# HIM-Otte-server-slow-control-V1-3a.net
KiCad netlist of a schematic drawn in EAGLE
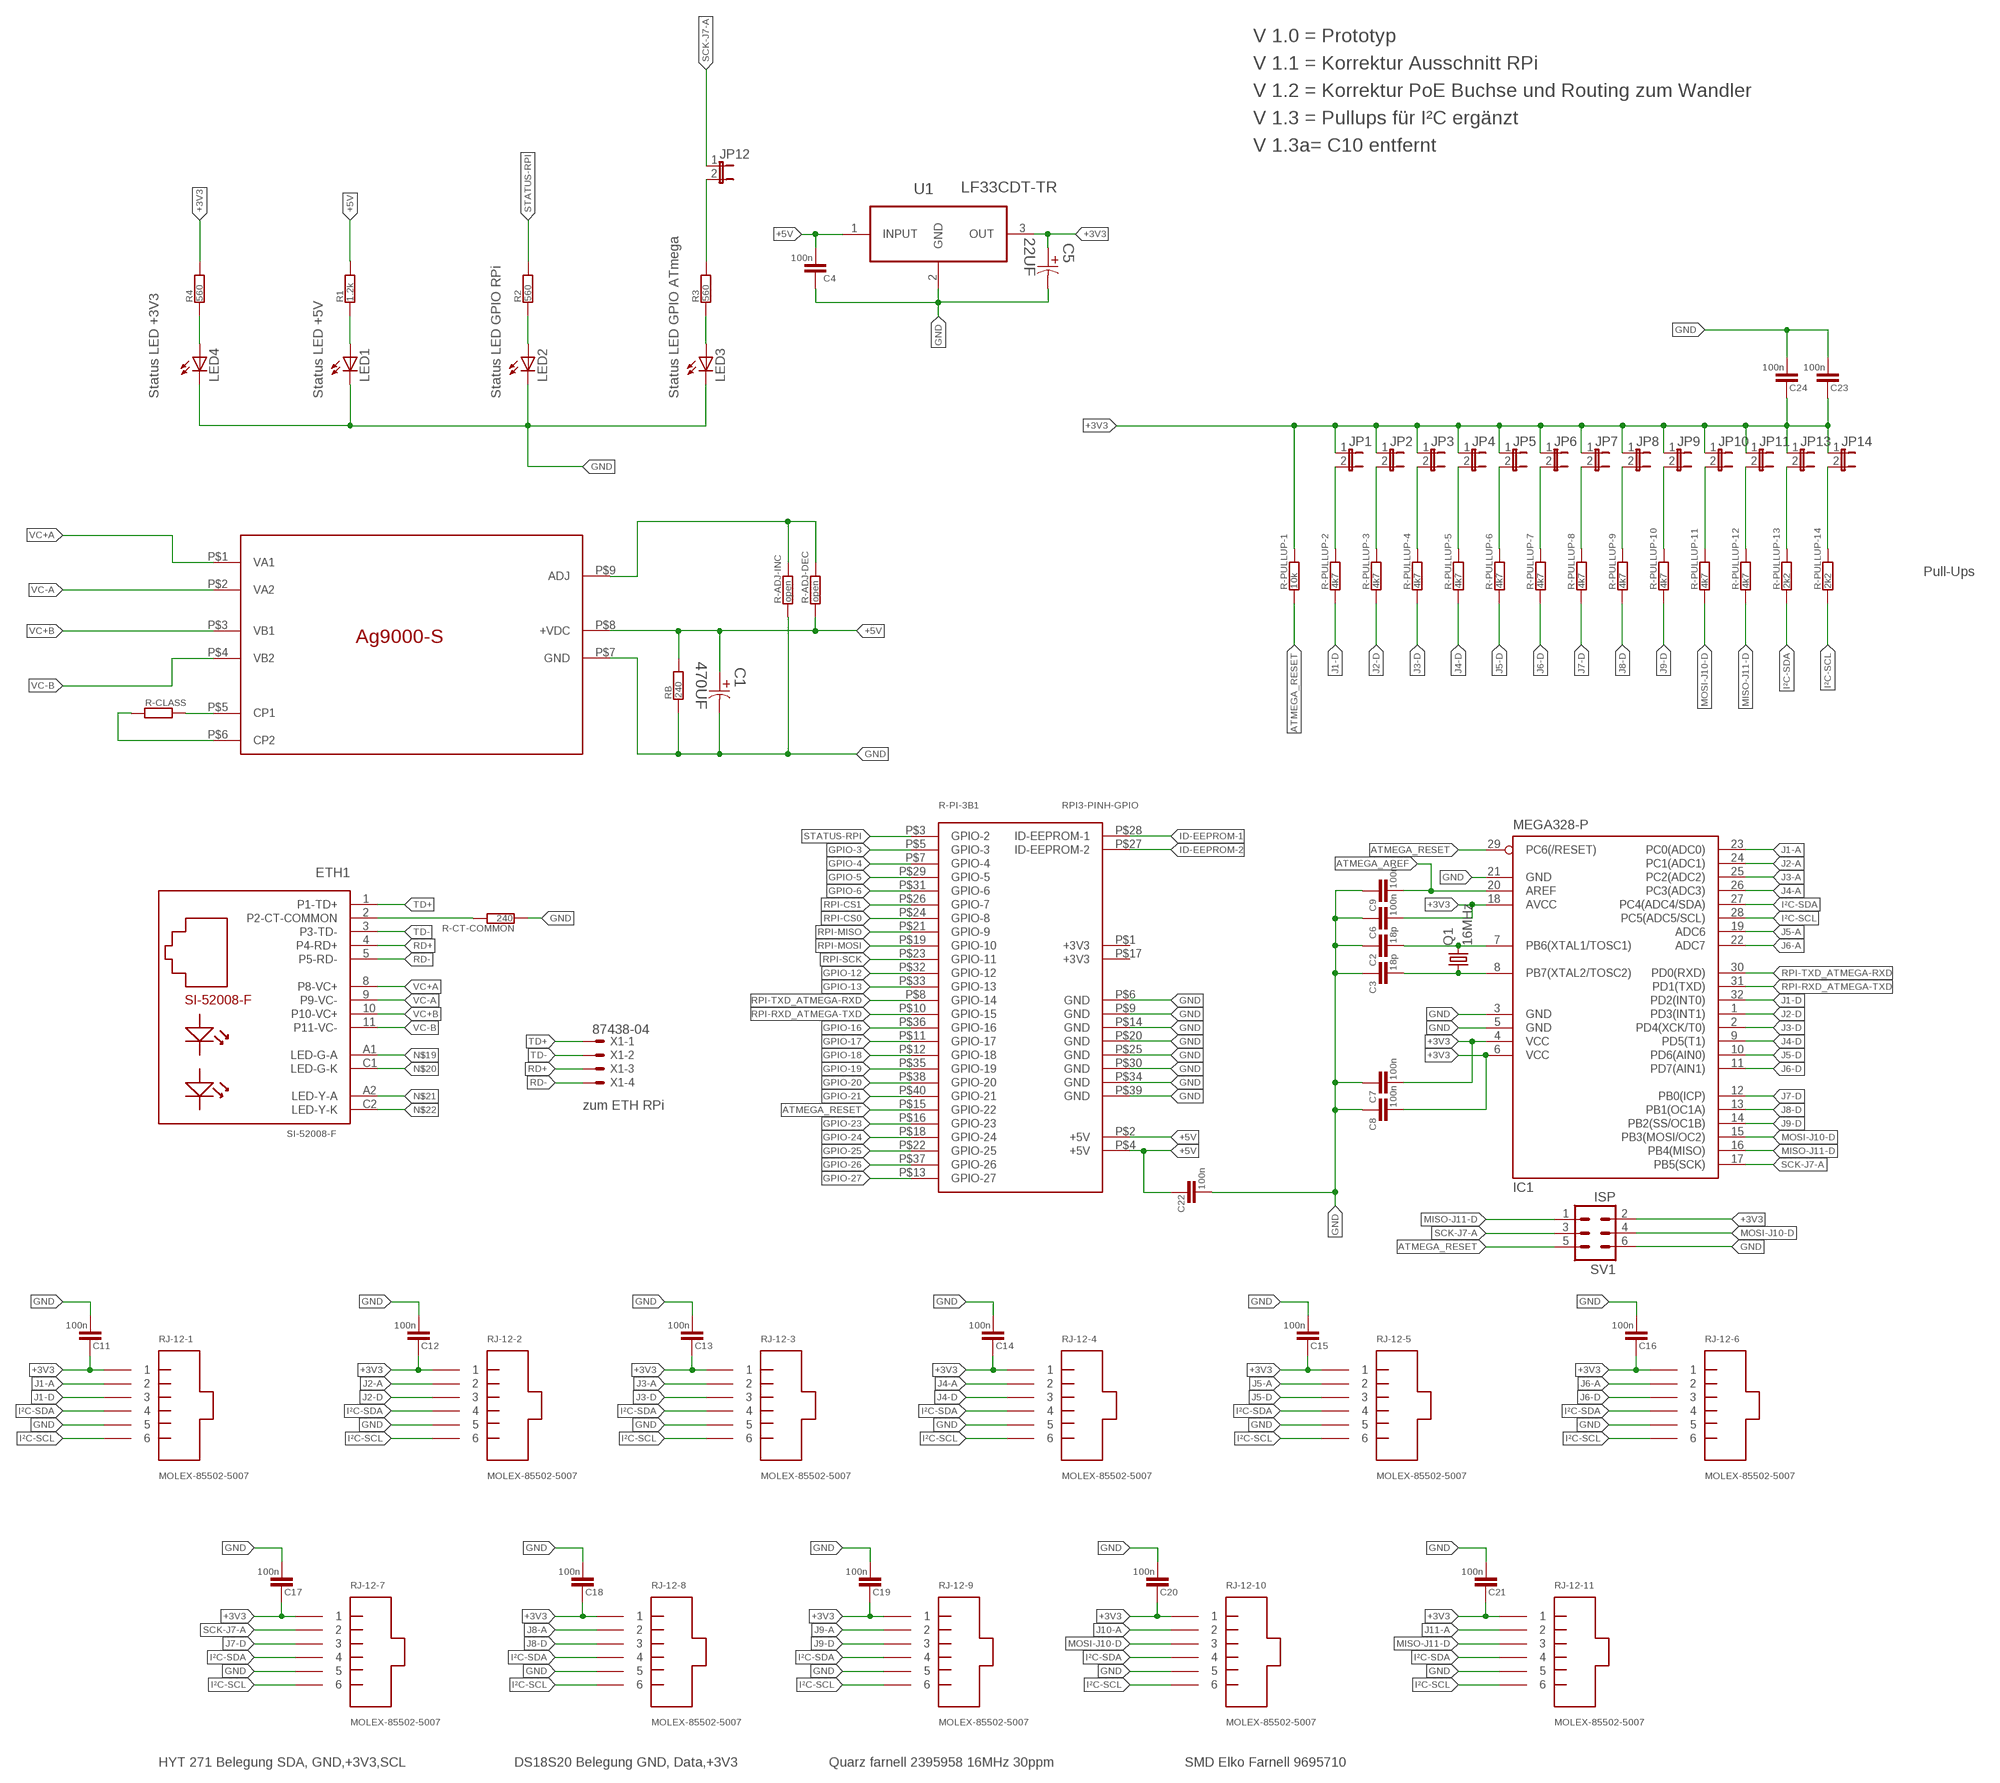
[diagram p0: schematic, sheet 1]

(export (version "E")
  (design (tool "Eeschema 10.0.6"))
  (components
    (comp (ref "C1")
      (value "470UF")
      (footprint "eagle-import:CAPAE830X1050N")
      (fields (field (name "MPN") "EEE-FK1C471P") (field (name "TOLERANCE") "±20 %"))
      (libsource (lib "eagle-import") (part "Panasonic-EEEFK_EEEFP_EEE--CASE-FFK1C471P"))
    )
    (comp (ref "C2")
      (value "18p")
      (footprint "eagle-import:C0603")
      (fields (field (name "TOLERANCE") "10%") (field (name "VOLTAGE") "16V"))
      (libsource (lib "eagle-import") (part "C-EUC0603"))
    )
    (comp (ref "C3")
      (value "18p")
      (footprint "eagle-import:C0603")
      (fields (field (name "TOLERANCE") "10%") (field (name "VOLTAGE") "16V"))
      (libsource (lib "eagle-import") (part "C-EUC0603"))
    )
    (comp (ref "C4")
      (value "100n")
      (footprint "eagle-import:C0603")
      (fields (field (name "TOLERANCE") "10%") (field (name "VOLTAGE") "16V"))
      (libsource (lib "eagle-import") (part "C-EUC0603"))
    )
    (comp (ref "C5")
      (value "22UF")
      (footprint "eagle-import:CAPAE530X610N")
      (fields (field (name "MPN") "EEE-FK1V220AR") (field (name "TOLERANCE") "±20 %"))
      (libsource (lib "eagle-import") (part "EEE--CASE-CFK1V220AR"))
    )
    (comp (ref "C6")
      (value "100n")
      (footprint "eagle-import:C0603")
      (fields (field (name "TOLERANCE") "10%") (field (name "VOLTAGE") "16V"))
      (libsource (lib "eagle-import") (part "C-EUC0603"))
    )
    (comp (ref "C7")
      (value "100n")
      (footprint "eagle-import:C0603")
      (fields (field (name "TOLERANCE") "10%") (field (name "VOLTAGE") "16V"))
      (libsource (lib "eagle-import") (part "C-EUC0603"))
    )
    (comp (ref "C8")
      (value "100n")
      (footprint "eagle-import:C0603")
      (fields (field (name "TOLERANCE") "10%") (field (name "VOLTAGE") "16V"))
      (libsource (lib "eagle-import") (part "C-EUC0603"))
    )
    (comp (ref "C9")
      (value "100n")
      (footprint "eagle-import:C0603")
      (fields (field (name "TOLERANCE") "10%") (field (name "VOLTAGE") "16V"))
      (libsource (lib "eagle-import") (part "C-EUC0603"))
    )
    (comp (ref "C11")
      (value "100n")
      (footprint "eagle-import:C0603")
      (fields (field (name "TOLERANCE") "10%") (field (name "VOLTAGE") "16V"))
      (libsource (lib "eagle-import") (part "C-EUC0603"))
    )
    (comp (ref "C12")
      (value "100n")
      (footprint "eagle-import:C0603")
      (fields (field (name "TOLERANCE") "10%") (field (name "VOLTAGE") "16V"))
      (libsource (lib "eagle-import") (part "C-EUC0603"))
    )
    (comp (ref "C13")
      (value "100n")
      (footprint "eagle-import:C0603")
      (fields (field (name "TOLERANCE") "10%") (field (name "VOLTAGE") "16V"))
      (libsource (lib "eagle-import") (part "C-EUC0603"))
    )
    (comp (ref "C14")
      (value "100n")
      (footprint "eagle-import:C0603")
      (fields (field (name "TOLERANCE") "10%") (field (name "VOLTAGE") "16V"))
      (libsource (lib "eagle-import") (part "C-EUC0603"))
    )
    (comp (ref "C15")
      (value "100n")
      (footprint "eagle-import:C0603")
      (fields (field (name "TOLERANCE") "10%") (field (name "VOLTAGE") "16V"))
      (libsource (lib "eagle-import") (part "C-EUC0603"))
    )
    (comp (ref "C16")
      (value "100n")
      (footprint "eagle-import:C0603")
      (fields (field (name "TOLERANCE") "10%") (field (name "VOLTAGE") "16V"))
      (libsource (lib "eagle-import") (part "C-EUC0603"))
    )
    (comp (ref "C17")
      (value "100n")
      (footprint "eagle-import:C0603")
      (fields (field (name "TOLERANCE") "10%") (field (name "VOLTAGE") "16V"))
      (libsource (lib "eagle-import") (part "C-EUC0603"))
    )
    (comp (ref "C18")
      (value "100n")
      (footprint "eagle-import:C0603")
      (fields (field (name "TOLERANCE") "10%") (field (name "VOLTAGE") "16V"))
      (libsource (lib "eagle-import") (part "C-EUC0603"))
    )
    (comp (ref "C19")
      (value "100n")
      (footprint "eagle-import:C0603")
      (fields (field (name "TOLERANCE") "10%") (field (name "VOLTAGE") "16V"))
      (libsource (lib "eagle-import") (part "C-EUC0603"))
    )
    (comp (ref "C20")
      (value "100n")
      (footprint "eagle-import:C0603")
      (fields (field (name "TOLERANCE") "10%") (field (name "VOLTAGE") "16V"))
      (libsource (lib "eagle-import") (part "C-EUC0603"))
    )
    (comp (ref "C21")
      (value "100n")
      (footprint "eagle-import:C0603")
      (fields (field (name "TOLERANCE") "10%") (field (name "VOLTAGE") "16V"))
      (libsource (lib "eagle-import") (part "C-EUC0603"))
    )
    (comp (ref "C22")
      (value "100n")
      (footprint "eagle-import:C0603")
      (fields (field (name "TOLERANCE") "10%") (field (name "VOLTAGE") "16V"))
      (libsource (lib "eagle-import") (part "C-EUC0603"))
    )
    (comp (ref "C23")
      (value "100n")
      (footprint "eagle-import:C0603")
      (fields (field (name "TOLERANCE") "10%") (field (name "VOLTAGE") "16V"))
      (libsource (lib "eagle-import") (part "C-EUC0603"))
    )
    (comp (ref "C24")
      (value "100n")
      (footprint "eagle-import:C0603")
      (fields (field (name "TOLERANCE") "10%") (field (name "VOLTAGE") "16V"))
      (libsource (lib "eagle-import") (part "C-EUC0603"))
    )
    (comp (ref "ETH1")
      (value "SI-52008-F")
      (footprint "eagle-import:SI-52008-F")
      (libsource (lib "eagle-import") (part "SI-52008-F"))
    )
    (comp (ref "IC1")
      (value "MEGA328-P")
      (footprint "eagle-import:TQFP32-08")
      (fields (field (name "MPN") "ATMEGA8-16AU"))
      (libsource (lib "eagle-import") (part "MEGA8-AI"))
    )
    (comp (ref "JP1")
      (value "JP1E")
      (footprint "eagle-import:JP1")
      (libsource (lib "eagle-import") (part "JP1E"))
    )
    (comp (ref "JP2")
      (value "JP1E")
      (footprint "eagle-import:JP1")
      (libsource (lib "eagle-import") (part "JP1E"))
    )
    (comp (ref "JP3")
      (value "JP1E")
      (footprint "eagle-import:JP1")
      (libsource (lib "eagle-import") (part "JP1E"))
    )
    (comp (ref "JP4")
      (value "JP1E")
      (footprint "eagle-import:JP1")
      (libsource (lib "eagle-import") (part "JP1E"))
    )
    (comp (ref "JP5")
      (value "JP1E")
      (footprint "eagle-import:JP1")
      (libsource (lib "eagle-import") (part "JP1E"))
    )
    (comp (ref "JP6")
      (value "JP1E")
      (footprint "eagle-import:JP1")
      (libsource (lib "eagle-import") (part "JP1E"))
    )
    (comp (ref "JP7")
      (value "JP1E")
      (footprint "eagle-import:JP1")
      (libsource (lib "eagle-import") (part "JP1E"))
    )
    (comp (ref "JP8")
      (value "JP1E")
      (footprint "eagle-import:JP1")
      (libsource (lib "eagle-import") (part "JP1E"))
    )
    (comp (ref "JP9")
      (value "JP1E")
      (footprint "eagle-import:JP1")
      (libsource (lib "eagle-import") (part "JP1E"))
    )
    (comp (ref "JP10")
      (value "JP1E")
      (footprint "eagle-import:JP1")
      (libsource (lib "eagle-import") (part "JP1E"))
    )
    (comp (ref "JP11")
      (value "JP1E")
      (footprint "eagle-import:JP1")
      (libsource (lib "eagle-import") (part "JP1E"))
    )
    (comp (ref "JP12")
      (value "JP1E")
      (footprint "eagle-import:JP1")
      (libsource (lib "eagle-import") (part "JP1E"))
    )
    (comp (ref "JP13")
      (value "JP1E")
      (footprint "eagle-import:JP1")
      (libsource (lib "eagle-import") (part "JP1E"))
    )
    (comp (ref "JP14")
      (value "JP1E")
      (footprint "eagle-import:JP1")
      (libsource (lib "eagle-import") (part "JP1E"))
    )
    (comp (ref "LED1")
      (value "LEDCHIPLED_0603")
      (footprint "eagle-import:CHIPLED_0603")
      (libsource (lib "eagle-import") (part "LEDCHIPLED_0603"))
    )
    (comp (ref "LED2")
      (value "LEDCHIPLED_0603")
      (footprint "eagle-import:CHIPLED_0603")
      (libsource (lib "eagle-import") (part "LEDCHIPLED_0603"))
    )
    (comp (ref "LED3")
      (value "LEDCHIPLED_0603")
      (footprint "eagle-import:CHIPLED_0603")
      (libsource (lib "eagle-import") (part "LEDCHIPLED_0603"))
    )
    (comp (ref "LED4")
      (value "LEDCHIPLED_0603")
      (footprint "eagle-import:CHIPLED_0603")
      (libsource (lib "eagle-import") (part "LEDCHIPLED_0603"))
    )
    (comp (ref "Q1")
      (value "16MHz")
      (footprint "eagle-import:HC49UP")
      (libsource (lib "eagle-import") (part "CRYSTALHC49UP"))
    )
    (comp (ref "R-ADJ-DEC")
      (value "open")
      (footprint "eagle-import:R0603")
      (fields (field (name "TOLERANCE") "1%"))
      (libsource (lib "eagle-import") (part "R-EU_R0603"))
    )
    (comp (ref "R-ADJ-INC")
      (value "open")
      (footprint "eagle-import:R0603")
      (fields (field (name "TOLERANCE") "1%"))
      (libsource (lib "eagle-import") (part "R-EU_R0603"))
    )
    (comp (ref "R-CLASS")
      (value "R-EU_R0603")
      (footprint "eagle-import:R0603")
      (fields (field (name "TOLERANCE") "1%"))
      (libsource (lib "eagle-import") (part "R-EU_R0603"))
    )
    (comp (ref "R-CT-COMMON")
      (value "240")
      (footprint "eagle-import:R0603")
      (fields (field (name "TOLERANCE") "1%"))
      (libsource (lib "eagle-import") (part "R-EU_R0603"))
    )
    (comp (ref "R-PI-3B1")
      (value "RPI3-PINH-GPIO")
      (footprint "eagle-import:RPI3-PINH-GPIO")
      (libsource (lib "eagle-import") (part "RPI3-PINH-GPIO"))
    )
    (comp (ref "R-PULLUP-1")
      (value "10k")
      (footprint "eagle-import:R0603")
      (fields (field (name "TOLERANCE") "1%"))
      (libsource (lib "eagle-import") (part "R-EU_R0603"))
    )
    (comp (ref "R-PULLUP-2")
      (value "4k7")
      (footprint "eagle-import:R0603")
      (fields (field (name "TOLERANCE") "1%"))
      (libsource (lib "eagle-import") (part "R-EU_R0603"))
    )
    (comp (ref "R-PULLUP-3")
      (value "4k7")
      (footprint "eagle-import:R0603")
      (fields (field (name "TOLERANCE") "1%"))
      (libsource (lib "eagle-import") (part "R-EU_R0603"))
    )
    (comp (ref "R-PULLUP-4")
      (value "4k7")
      (footprint "eagle-import:R0603")
      (fields (field (name "TOLERANCE") "1%"))
      (libsource (lib "eagle-import") (part "R-EU_R0603"))
    )
    (comp (ref "R-PULLUP-5")
      (value "4k7")
      (footprint "eagle-import:R0603")
      (fields (field (name "TOLERANCE") "1%"))
      (libsource (lib "eagle-import") (part "R-EU_R0603"))
    )
    (comp (ref "R-PULLUP-6")
      (value "4k7")
      (footprint "eagle-import:R0603")
      (fields (field (name "TOLERANCE") "1%"))
      (libsource (lib "eagle-import") (part "R-EU_R0603"))
    )
    (comp (ref "R-PULLUP-7")
      (value "4k7")
      (footprint "eagle-import:R0603")
      (fields (field (name "TOLERANCE") "1%"))
      (libsource (lib "eagle-import") (part "R-EU_R0603"))
    )
    (comp (ref "R-PULLUP-8")
      (value "4k7")
      (footprint "eagle-import:R0603")
      (fields (field (name "TOLERANCE") "1%"))
      (libsource (lib "eagle-import") (part "R-EU_R0603"))
    )
    (comp (ref "R-PULLUP-9")
      (value "4k7")
      (footprint "eagle-import:R0603")
      (fields (field (name "TOLERANCE") "1%"))
      (libsource (lib "eagle-import") (part "R-EU_R0603"))
    )
    (comp (ref "R-PULLUP-10")
      (value "4k7")
      (footprint "eagle-import:R0603")
      (fields (field (name "TOLERANCE") "1%"))
      (libsource (lib "eagle-import") (part "R-EU_R0603"))
    )
    (comp (ref "R-PULLUP-11")
      (value "4k7")
      (footprint "eagle-import:R0603")
      (fields (field (name "TOLERANCE") "1%"))
      (libsource (lib "eagle-import") (part "R-EU_R0603"))
    )
    (comp (ref "R-PULLUP-12")
      (value "4k7")
      (footprint "eagle-import:R0603")
      (fields (field (name "TOLERANCE") "1%"))
      (libsource (lib "eagle-import") (part "R-EU_R0603"))
    )
    (comp (ref "R-PULLUP-13")
      (value "2k2")
      (footprint "eagle-import:R0603")
      (fields (field (name "TOLERANCE") "1%"))
      (libsource (lib "eagle-import") (part "R-EU_R0603"))
    )
    (comp (ref "R-PULLUP-14")
      (value "2k2")
      (footprint "eagle-import:R0603")
      (fields (field (name "TOLERANCE") "1%"))
      (libsource (lib "eagle-import") (part "R-EU_R0603"))
    )
    (comp (ref "R1")
      (value "1.2k")
      (footprint "eagle-import:R0603")
      (fields (field (name "TOLERANCE") "1%"))
      (libsource (lib "eagle-import") (part "R-EU_R0603"))
    )
    (comp (ref "R2")
      (value "560")
      (footprint "eagle-import:R0603")
      (fields (field (name "TOLERANCE") "1%"))
      (libsource (lib "eagle-import") (part "R-EU_R0603"))
    )
    (comp (ref "R3")
      (value "560")
      (footprint "eagle-import:R0603")
      (fields (field (name "TOLERANCE") "1%"))
      (libsource (lib "eagle-import") (part "R-EU_R0603"))
    )
    (comp (ref "R4")
      (value "560")
      (footprint "eagle-import:R0603")
      (fields (field (name "TOLERANCE") "1%"))
      (libsource (lib "eagle-import") (part "R-EU_R0603"))
    )
    (comp (ref "RB")
      (value "240")
      (footprint "eagle-import:R0603")
      (fields (field (name "TOLERANCE") "1%"))
      (libsource (lib "eagle-import") (part "R-EU_R0603"))
    )
    (comp (ref "RJ-12-1")
      (value "MOLEX-85502-5007")
      (footprint "eagle-import:MOLEX-85502-5007")
      (libsource (lib "eagle-import") (part "MOLEX-85502-5007"))
    )
    (comp (ref "RJ-12-2")
      (value "MOLEX-85502-5007")
      (footprint "eagle-import:MOLEX-85502-5007")
      (libsource (lib "eagle-import") (part "MOLEX-85502-5007"))
    )
    (comp (ref "RJ-12-3")
      (value "MOLEX-85502-5007")
      (footprint "eagle-import:MOLEX-85502-5007")
      (libsource (lib "eagle-import") (part "MOLEX-85502-5007"))
    )
    (comp (ref "RJ-12-4")
      (value "MOLEX-85502-5007")
      (footprint "eagle-import:MOLEX-85502-5007")
      (libsource (lib "eagle-import") (part "MOLEX-85502-5007"))
    )
    (comp (ref "RJ-12-5")
      (value "MOLEX-85502-5007")
      (footprint "eagle-import:MOLEX-85502-5007")
      (libsource (lib "eagle-import") (part "MOLEX-85502-5007"))
    )
    (comp (ref "RJ-12-6")
      (value "MOLEX-85502-5007")
      (footprint "eagle-import:MOLEX-85502-5007")
      (libsource (lib "eagle-import") (part "MOLEX-85502-5007"))
    )
    (comp (ref "RJ-12-7")
      (value "MOLEX-85502-5007")
      (footprint "eagle-import:MOLEX-85502-5007")
      (libsource (lib "eagle-import") (part "MOLEX-85502-5007"))
    )
    (comp (ref "RJ-12-8")
      (value "MOLEX-85502-5007")
      (footprint "eagle-import:MOLEX-85502-5007")
      (libsource (lib "eagle-import") (part "MOLEX-85502-5007"))
    )
    (comp (ref "RJ-12-9")
      (value "MOLEX-85502-5007")
      (footprint "eagle-import:MOLEX-85502-5007")
      (libsource (lib "eagle-import") (part "MOLEX-85502-5007"))
    )
    (comp (ref "RJ-12-10")
      (value "MOLEX-85502-5007")
      (footprint "eagle-import:MOLEX-85502-5007")
      (libsource (lib "eagle-import") (part "MOLEX-85502-5007"))
    )
    (comp (ref "RJ-12-11")
      (value "MOLEX-85502-5007")
      (footprint "eagle-import:MOLEX-85502-5007")
      (libsource (lib "eagle-import") (part "MOLEX-85502-5007"))
    )
    (comp (ref "SV1")
      (value "ISP")
      (footprint "eagle-import:ML6")
      (libsource (lib "eagle-import") (part "ML6"))
    )
    (comp (ref "U$1")
      (value "AG9000-S")
      (footprint "eagle-import:AG9000-S")
      (libsource (lib "eagle-import") (part "AG9000-S"))
    )
    (comp (ref "U1")
      (value "LF33CDT-TR")
      (footprint "eagle-import:TO228P972X240-3N")
      (libsource (lib "eagle-import") (part "LF33CDT-TR"))
    )
    (comp (ref "X1")
      (value "87438-04")
      (footprint "eagle-import:87438-04")
      (libsource (lib "eagle-import") (part "87438-04"))
    )
  )
  (nets
    (net (code "1") (name "+3V3") (class "Default")
      (node (ref "C11") (pin "1") (pinfunction "1_1") (pintype "passive"))
      (node (ref "C12") (pin "1") (pinfunction "1_1") (pintype "passive"))
      (node (ref "C13") (pin "1") (pinfunction "1_1") (pintype "passive"))
      (node (ref "C14") (pin "1") (pinfunction "1_1") (pintype "passive"))
      (node (ref "C15") (pin "1") (pinfunction "1_1") (pintype "passive"))
      (node (ref "C16") (pin "1") (pinfunction "1_1") (pintype "passive"))
      (node (ref "C17") (pin "1") (pinfunction "1_1") (pintype "passive"))
      (node (ref "C18") (pin "1") (pinfunction "1_1") (pintype "passive"))
      (node (ref "C19") (pin "1") (pinfunction "1_1") (pintype "passive"))
      (node (ref "C20") (pin "1") (pinfunction "1_1") (pintype "passive"))
      (node (ref "C21") (pin "1") (pinfunction "1_1") (pintype "passive"))
      (node (ref "C23") (pin "1") (pinfunction "1_1") (pintype "passive"))
      (node (ref "C24") (pin "1") (pinfunction "1_1") (pintype "passive"))
      (node (ref "C5") (pin "1") (pinfunction "1_1") (pintype "passive"))
      (node (ref "C6") (pin "2") (pinfunction "2_2") (pintype "passive"))
      (node (ref "C7") (pin "2") (pinfunction "2_2") (pintype "passive"))
      (node (ref "C8") (pin "2") (pinfunction "2_2") (pintype "passive"))
      (node (ref "IC1") (pin "18") (pinfunction "AVCC_18") (pintype "power_in"))
      (node (ref "IC1") (pin "4") (pinfunction "VCC_4") (pintype "power_in"))
      (node (ref "IC1") (pin "6") (pinfunction "VCC_6") (pintype "power_in"))
      (node (ref "JP1") (pin "1") (pinfunction "1_1") (pintype "passive"))
      (node (ref "JP10") (pin "1") (pinfunction "1_1") (pintype "passive"))
      (node (ref "JP11") (pin "1") (pinfunction "1_1") (pintype "passive"))
      (node (ref "JP13") (pin "1") (pinfunction "1_1") (pintype "passive"))
      (node (ref "JP14") (pin "1") (pinfunction "1_1") (pintype "passive"))
      (node (ref "JP2") (pin "1") (pinfunction "1_1") (pintype "passive"))
      (node (ref "JP3") (pin "1") (pinfunction "1_1") (pintype "passive"))
      (node (ref "JP4") (pin "1") (pinfunction "1_1") (pintype "passive"))
      (node (ref "JP5") (pin "1") (pinfunction "1_1") (pintype "passive"))
      (node (ref "JP6") (pin "1") (pinfunction "1_1") (pintype "passive"))
      (node (ref "JP7") (pin "1") (pinfunction "1_1") (pintype "passive"))
      (node (ref "JP8") (pin "1") (pinfunction "1_1") (pintype "passive"))
      (node (ref "JP9") (pin "1") (pinfunction "1_1") (pintype "passive"))
      (node (ref "R-PULLUP-1") (pin "2") (pinfunction "2_2") (pintype "passive"))
      (node (ref "R4") (pin "2") (pinfunction "2_2") (pintype "passive"))
      (node (ref "RJ-12-1") (pin "1") (pinfunction "1_1") (pintype "bidirectional"))
      (node (ref "RJ-12-10") (pin "1") (pinfunction "1_1") (pintype "bidirectional"))
      (node (ref "RJ-12-11") (pin "1") (pinfunction "1_1") (pintype "bidirectional"))
      (node (ref "RJ-12-2") (pin "1") (pinfunction "1_1") (pintype "bidirectional"))
      (node (ref "RJ-12-3") (pin "1") (pinfunction "1_1") (pintype "bidirectional"))
      (node (ref "RJ-12-4") (pin "1") (pinfunction "1_1") (pintype "bidirectional"))
      (node (ref "RJ-12-5") (pin "1") (pinfunction "1_1") (pintype "bidirectional"))
      (node (ref "RJ-12-6") (pin "1") (pinfunction "1_1") (pintype "bidirectional"))
      (node (ref "RJ-12-7") (pin "1") (pinfunction "1_1") (pintype "bidirectional"))
      (node (ref "RJ-12-8") (pin "1") (pinfunction "1_1") (pintype "bidirectional"))
      (node (ref "RJ-12-9") (pin "1") (pinfunction "1_1") (pintype "bidirectional"))
      (node (ref "SV1") (pin "2") (pinfunction "2_2") (pintype "passive"))
      (node (ref "U1") (pin "3") (pinfunction "OUT_3") (pintype "output"))
    )
    (net (code "2") (name "+5V") (class "Default")
      (node (ref "C1") (pin "1") (pinfunction "1_1") (pintype "passive"))
      (node (ref "C22") (pin "1") (pinfunction "1_1") (pintype "passive"))
      (node (ref "C4") (pin "2") (pinfunction "2_2") (pintype "passive"))
      (node (ref "R-ADJ-DEC") (pin "1") (pinfunction "1_1") (pintype "passive"))
      (node (ref "R-PI-3B1") (pin "P$2") (pinfunction "+5V_P$2") (pintype "bidirectional"))
      (node (ref "R-PI-3B1") (pin "P$4") (pinfunction "+5V_P$4") (pintype "bidirectional"))
      (node (ref "R1") (pin "2") (pinfunction "2_2") (pintype "passive"))
      (node (ref "RB") (pin "2") (pinfunction "2_2") (pintype "passive"))
      (node (ref "U$1") (pin "P$8") (pinfunction "+VDC_P$8") (pintype "output"))
      (node (ref "U1") (pin "1") (pinfunction "INPUT_1") (pintype "input"))
    )
    (net (code "3") (name "ATMEGA_AREF") (class "Default")
      (node (ref "C9") (pin "2") (pinfunction "2_2") (pintype "passive"))
      (node (ref "IC1") (pin "20") (pinfunction "AREF_20") (pintype "passive"))
    )
    (net (code "4") (name "ATMEGA_RESET") (class "Default")
      (node (ref "IC1") (pin "29") (pinfunction "PC6(/RESET)_29") (pintype "bidirectional"))
      (node (ref "R-PI-3B1") (pin "P$15") (pinfunction "GPIO-22_P$15") (pintype "bidirectional"))
      (node (ref "R-PULLUP-1") (pin "1") (pinfunction "1_1") (pintype "passive"))
      (node (ref "SV1") (pin "5") (pinfunction "5_5") (pintype "passive"))
    )
    (net (code "5") (name "GND") (class "Default")
      (node (ref "C1") (pin "2") (pinfunction "2_2") (pintype "passive"))
      (node (ref "C11") (pin "2") (pinfunction "2_2") (pintype "passive"))
      (node (ref "C12") (pin "2") (pinfunction "2_2") (pintype "passive"))
      (node (ref "C13") (pin "2") (pinfunction "2_2") (pintype "passive"))
      (node (ref "C14") (pin "2") (pinfunction "2_2") (pintype "passive"))
      (node (ref "C15") (pin "2") (pinfunction "2_2") (pintype "passive"))
      (node (ref "C16") (pin "2") (pinfunction "2_2") (pintype "passive"))
      (node (ref "C17") (pin "2") (pinfunction "2_2") (pintype "passive"))
      (node (ref "C18") (pin "2") (pinfunction "2_2") (pintype "passive"))
      (node (ref "C19") (pin "2") (pinfunction "2_2") (pintype "passive"))
      (node (ref "C2") (pin "1") (pinfunction "1_1") (pintype "passive"))
      (node (ref "C20") (pin "2") (pinfunction "2_2") (pintype "passive"))
      (node (ref "C21") (pin "2") (pinfunction "2_2") (pintype "passive"))
      (node (ref "C22") (pin "2") (pinfunction "2_2") (pintype "passive"))
      (node (ref "C23") (pin "2") (pinfunction "2_2") (pintype "passive"))
      (node (ref "C24") (pin "2") (pinfunction "2_2") (pintype "passive"))
      (node (ref "C3") (pin "1") (pinfunction "1_1") (pintype "passive"))
      (node (ref "C4") (pin "1") (pinfunction "1_1") (pintype "passive"))
      (node (ref "C5") (pin "2") (pinfunction "2_2") (pintype "passive"))
      (node (ref "C6") (pin "1") (pinfunction "1_1") (pintype "passive"))
      (node (ref "C7") (pin "1") (pinfunction "1_1") (pintype "passive"))
      (node (ref "C8") (pin "1") (pinfunction "1_1") (pintype "passive"))
      (node (ref "C9") (pin "1") (pinfunction "1_1") (pintype "passive"))
      (node (ref "IC1") (pin "21") (pinfunction "GND_21") (pintype "power_in"))
      (node (ref "IC1") (pin "3") (pinfunction "GND_3") (pintype "power_in"))
      (node (ref "IC1") (pin "5") (pinfunction "GND_5") (pintype "power_in"))
      (node (ref "LED1") (pin "C") (pinfunction "C_C") (pintype "passive"))
      (node (ref "LED2") (pin "C") (pinfunction "C_C") (pintype "passive"))
      (node (ref "LED3") (pin "C") (pinfunction "C_C") (pintype "passive"))
      (node (ref "LED4") (pin "C") (pinfunction "C_C") (pintype "passive"))
      (node (ref "R-ADJ-INC") (pin "1") (pinfunction "1_1") (pintype "passive"))
      (node (ref "R-CT-COMMON") (pin "1") (pinfunction "1_1") (pintype "passive"))
      (node (ref "R-PI-3B1") (pin "P$14") (pinfunction "GND_P$14") (pintype "bidirectional"))
      (node (ref "R-PI-3B1") (pin "P$20") (pinfunction "GND_P$20") (pintype "bidirectional"))
      (node (ref "R-PI-3B1") (pin "P$25") (pinfunction "GND_P$25") (pintype "bidirectional"))
      (node (ref "R-PI-3B1") (pin "P$30") (pinfunction "GND_P$30") (pintype "bidirectional"))
      (node (ref "R-PI-3B1") (pin "P$34") (pinfunction "GND_P$34") (pintype "bidirectional"))
      (node (ref "R-PI-3B1") (pin "P$39") (pinfunction "GND_P$39") (pintype "bidirectional"))
      (node (ref "R-PI-3B1") (pin "P$6") (pinfunction "GND_P$6") (pintype "bidirectional"))
      (node (ref "R-PI-3B1") (pin "P$9") (pinfunction "GND_P$9") (pintype "bidirectional"))
      (node (ref "RB") (pin "1") (pinfunction "1_1") (pintype "passive"))
      (node (ref "RJ-12-1") (pin "5") (pinfunction "5_5") (pintype "bidirectional"))
      (node (ref "RJ-12-10") (pin "5") (pinfunction "5_5") (pintype "bidirectional"))
      (node (ref "RJ-12-11") (pin "5") (pinfunction "5_5") (pintype "bidirectional"))
      (node (ref "RJ-12-2") (pin "5") (pinfunction "5_5") (pintype "bidirectional"))
      (node (ref "RJ-12-3") (pin "5") (pinfunction "5_5") (pintype "bidirectional"))
      (node (ref "RJ-12-4") (pin "5") (pinfunction "5_5") (pintype "bidirectional"))
      (node (ref "RJ-12-5") (pin "5") (pinfunction "5_5") (pintype "bidirectional"))
      (node (ref "RJ-12-6") (pin "5") (pinfunction "5_5") (pintype "bidirectional"))
      (node (ref "RJ-12-7") (pin "5") (pinfunction "5_5") (pintype "bidirectional"))
      (node (ref "RJ-12-8") (pin "5") (pinfunction "5_5") (pintype "bidirectional"))
      (node (ref "RJ-12-9") (pin "5") (pinfunction "5_5") (pintype "bidirectional"))
      (node (ref "SV1") (pin "6") (pinfunction "6_6") (pintype "passive"))
      (node (ref "U$1") (pin "P$7") (pinfunction "GND_P$7") (pintype "output"))
      (node (ref "U1") (pin "2") (pinfunction "GND_2") (pintype "passive"))
    )
    (net (code "6") (name "GPIO-3") (class "Default")
      (node (ref "R-PI-3B1") (pin "P$5") (pinfunction "GPIO-3_P$5") (pintype "bidirectional"))
    )
    (net (code "7") (name "GPIO-4") (class "Default")
      (node (ref "R-PI-3B1") (pin "P$7") (pinfunction "GPIO-4_P$7") (pintype "bidirectional"))
    )
    (net (code "8") (name "GPIO-5") (class "Default")
      (node (ref "R-PI-3B1") (pin "P$29") (pinfunction "GPIO-5_P$29") (pintype "bidirectional"))
    )
    (net (code "9") (name "GPIO-6") (class "Default")
      (node (ref "R-PI-3B1") (pin "P$31") (pinfunction "GPIO-6_P$31") (pintype "bidirectional"))
    )
    (net (code "10") (name "GPIO-12") (class "Default")
      (node (ref "R-PI-3B1") (pin "P$32") (pinfunction "GPIO-12_P$32") (pintype "bidirectional"))
    )
    (net (code "11") (name "GPIO-13") (class "Default")
      (node (ref "R-PI-3B1") (pin "P$33") (pinfunction "GPIO-13_P$33") (pintype "bidirectional"))
    )
    (net (code "12") (name "GPIO-16") (class "Default")
      (node (ref "R-PI-3B1") (pin "P$36") (pinfunction "GPIO-16_P$36") (pintype "bidirectional"))
    )
    (net (code "13") (name "GPIO-17") (class "Default")
      (node (ref "R-PI-3B1") (pin "P$11") (pinfunction "GPIO-17_P$11") (pintype "bidirectional"))
    )
    (net (code "14") (name "GPIO-18") (class "Default")
      (node (ref "R-PI-3B1") (pin "P$12") (pinfunction "GPIO-18_P$12") (pintype "bidirectional"))
    )
    (net (code "15") (name "GPIO-19") (class "Default")
      (node (ref "R-PI-3B1") (pin "P$35") (pinfunction "GPIO-19_P$35") (pintype "bidirectional"))
    )
    (net (code "16") (name "GPIO-20") (class "Default")
      (node (ref "R-PI-3B1") (pin "P$38") (pinfunction "GPIO-20_P$38") (pintype "bidirectional"))
    )
    (net (code "17") (name "GPIO-21") (class "Default")
      (node (ref "R-PI-3B1") (pin "P$40") (pinfunction "GPIO-21_P$40") (pintype "bidirectional"))
    )
    (net (code "18") (name "GPIO-23") (class "Default")
      (node (ref "R-PI-3B1") (pin "P$16") (pinfunction "GPIO-23_P$16") (pintype "bidirectional"))
    )
    (net (code "19") (name "GPIO-24") (class "Default")
      (node (ref "R-PI-3B1") (pin "P$18") (pinfunction "GPIO-24_P$18") (pintype "bidirectional"))
    )
    (net (code "20") (name "GPIO-25") (class "Default")
      (node (ref "R-PI-3B1") (pin "P$22") (pinfunction "GPIO-25_P$22") (pintype "bidirectional"))
    )
    (net (code "21") (name "GPIO-26") (class "Default")
      (node (ref "R-PI-3B1") (pin "P$37") (pinfunction "GPIO-26_P$37") (pintype "bidirectional"))
    )
    (net (code "22") (name "GPIO-27") (class "Default")
      (node (ref "R-PI-3B1") (pin "P$13") (pinfunction "GPIO-27_P$13") (pintype "bidirectional"))
    )
    (net (code "23") (name "ID-EEPROM-1") (class "Default")
      (node (ref "R-PI-3B1") (pin "P$28") (pinfunction "ID-EEPROM-1_P$28") (pintype "bidirectional"))
    )
    (net (code "24") (name "ID-EEPROM-2") (class "Default")
      (node (ref "R-PI-3B1") (pin "P$27") (pinfunction "ID-EEPROM-2_P$27") (pintype "bidirectional"))
    )
    (net (code "25") (name "I²C-SCL") (class "Default")
      (node (ref "IC1") (pin "28") (pinfunction "PC5(ADC5/SCL)_28") (pintype "bidirectional"))
      (node (ref "R-PULLUP-14") (pin "1") (pinfunction "1_1") (pintype "passive"))
      (node (ref "RJ-12-1") (pin "6") (pinfunction "6_6") (pintype "bidirectional"))
      (node (ref "RJ-12-10") (pin "6") (pinfunction "6_6") (pintype "bidirectional"))
      (node (ref "RJ-12-11") (pin "6") (pinfunction "6_6") (pintype "bidirectional"))
      (node (ref "RJ-12-2") (pin "6") (pinfunction "6_6") (pintype "bidirectional"))
      (node (ref "RJ-12-3") (pin "6") (pinfunction "6_6") (pintype "bidirectional"))
      (node (ref "RJ-12-4") (pin "6") (pinfunction "6_6") (pintype "bidirectional"))
      (node (ref "RJ-12-5") (pin "6") (pinfunction "6_6") (pintype "bidirectional"))
      (node (ref "RJ-12-6") (pin "6") (pinfunction "6_6") (pintype "bidirectional"))
      (node (ref "RJ-12-7") (pin "6") (pinfunction "6_6") (pintype "bidirectional"))
      (node (ref "RJ-12-8") (pin "6") (pinfunction "6_6") (pintype "bidirectional"))
      (node (ref "RJ-12-9") (pin "6") (pinfunction "6_6") (pintype "bidirectional"))
    )
    (net (code "26") (name "I²C-SDA") (class "Default")
      (node (ref "IC1") (pin "27") (pinfunction "PC4(ADC4/SDA)_27") (pintype "bidirectional"))
      (node (ref "R-PULLUP-13") (pin "1") (pinfunction "1_1") (pintype "passive"))
      (node (ref "RJ-12-1") (pin "4") (pinfunction "4_4") (pintype "bidirectional"))
      (node (ref "RJ-12-10") (pin "4") (pinfunction "4_4") (pintype "bidirectional"))
      (node (ref "RJ-12-11") (pin "4") (pinfunction "4_4") (pintype "bidirectional"))
      (node (ref "RJ-12-2") (pin "4") (pinfunction "4_4") (pintype "bidirectional"))
      (node (ref "RJ-12-3") (pin "4") (pinfunction "4_4") (pintype "bidirectional"))
      (node (ref "RJ-12-4") (pin "4") (pinfunction "4_4") (pintype "bidirectional"))
      (node (ref "RJ-12-5") (pin "4") (pinfunction "4_4") (pintype "bidirectional"))
      (node (ref "RJ-12-6") (pin "4") (pinfunction "4_4") (pintype "bidirectional"))
      (node (ref "RJ-12-7") (pin "4") (pinfunction "4_4") (pintype "bidirectional"))
      (node (ref "RJ-12-8") (pin "4") (pinfunction "4_4") (pintype "bidirectional"))
      (node (ref "RJ-12-9") (pin "4") (pinfunction "4_4") (pintype "bidirectional"))
    )
    (net (code "27") (name "J1-A") (class "Default")
      (node (ref "IC1") (pin "23") (pinfunction "PC0(ADC0)_23") (pintype "bidirectional"))
      (node (ref "RJ-12-1") (pin "2") (pinfunction "2_2") (pintype "bidirectional"))
    )
    (net (code "28") (name "J1-D") (class "Default")
      (node (ref "IC1") (pin "32") (pinfunction "PD2(INT0)_32") (pintype "bidirectional"))
      (node (ref "R-PULLUP-2") (pin "1") (pinfunction "1_1") (pintype "passive"))
      (node (ref "RJ-12-1") (pin "3") (pinfunction "3_3") (pintype "bidirectional"))
    )
    (net (code "29") (name "J2-A") (class "Default")
      (node (ref "IC1") (pin "24") (pinfunction "PC1(ADC1)_24") (pintype "bidirectional"))
      (node (ref "RJ-12-2") (pin "2") (pinfunction "2_2") (pintype "bidirectional"))
    )
    (net (code "30") (name "J2-D") (class "Default")
      (node (ref "IC1") (pin "1") (pinfunction "PD3(INT1)_1") (pintype "bidirectional"))
      (node (ref "R-PULLUP-3") (pin "1") (pinfunction "1_1") (pintype "passive"))
      (node (ref "RJ-12-2") (pin "3") (pinfunction "3_3") (pintype "bidirectional"))
    )
    (net (code "31") (name "J3-A") (class "Default")
      (node (ref "IC1") (pin "25") (pinfunction "PC2(ADC2)_25") (pintype "bidirectional"))
      (node (ref "RJ-12-3") (pin "2") (pinfunction "2_2") (pintype "bidirectional"))
    )
    (net (code "32") (name "J3-D") (class "Default")
      (node (ref "IC1") (pin "2") (pinfunction "PD4(XCK/T0)_2") (pintype "bidirectional"))
      (node (ref "R-PULLUP-4") (pin "1") (pinfunction "1_1") (pintype "passive"))
      (node (ref "RJ-12-3") (pin "3") (pinfunction "3_3") (pintype "bidirectional"))
    )
    (net (code "33") (name "J4-A") (class "Default")
      (node (ref "IC1") (pin "26") (pinfunction "PC3(ADC3)_26") (pintype "bidirectional"))
      (node (ref "RJ-12-4") (pin "2") (pinfunction "2_2") (pintype "bidirectional"))
    )
    (net (code "34") (name "J4-D") (class "Default")
      (node (ref "IC1") (pin "9") (pinfunction "PD5(T1)_9") (pintype "bidirectional"))
      (node (ref "R-PULLUP-5") (pin "1") (pinfunction "1_1") (pintype "passive"))
      (node (ref "RJ-12-4") (pin "3") (pinfunction "3_3") (pintype "bidirectional"))
    )
    (net (code "35") (name "J5-A") (class "Default")
      (node (ref "IC1") (pin "19") (pinfunction "ADC6_19") (pintype "bidirectional"))
      (node (ref "RJ-12-5") (pin "2") (pinfunction "2_2") (pintype "bidirectional"))
    )
    (net (code "36") (name "J5-D") (class "Default")
      (node (ref "IC1") (pin "10") (pinfunction "PD6(AIN0)_10") (pintype "bidirectional"))
      (node (ref "R-PULLUP-6") (pin "1") (pinfunction "1_1") (pintype "passive"))
      (node (ref "RJ-12-5") (pin "3") (pinfunction "3_3") (pintype "bidirectional"))
    )
    (net (code "37") (name "J6-A") (class "Default")
      (node (ref "IC1") (pin "22") (pinfunction "ADC7_22") (pintype "bidirectional"))
      (node (ref "RJ-12-6") (pin "2") (pinfunction "2_2") (pintype "bidirectional"))
    )
    (net (code "38") (name "J6-D") (class "Default")
      (node (ref "IC1") (pin "11") (pinfunction "PD7(AIN1)_11") (pintype "bidirectional"))
      (node (ref "R-PULLUP-7") (pin "1") (pinfunction "1_1") (pintype "passive"))
      (node (ref "RJ-12-6") (pin "3") (pinfunction "3_3") (pintype "bidirectional"))
    )
    (net (code "39") (name "J7-D") (class "Default")
      (node (ref "IC1") (pin "12") (pinfunction "PB0(ICP)_12") (pintype "bidirectional"))
      (node (ref "R-PULLUP-8") (pin "1") (pinfunction "1_1") (pintype "passive"))
      (node (ref "RJ-12-7") (pin "3") (pinfunction "3_3") (pintype "bidirectional"))
    )
    (net (code "40") (name "J8-A") (class "Default")
      (node (ref "RJ-12-8") (pin "2") (pinfunction "2_2") (pintype "bidirectional"))
    )
    (net (code "41") (name "J8-D") (class "Default")
      (node (ref "IC1") (pin "13") (pinfunction "PB1(OC1A)_13") (pintype "bidirectional"))
      (node (ref "R-PULLUP-9") (pin "1") (pinfunction "1_1") (pintype "passive"))
      (node (ref "RJ-12-8") (pin "3") (pinfunction "3_3") (pintype "bidirectional"))
    )
    (net (code "42") (name "J9-A") (class "Default")
      (node (ref "RJ-12-9") (pin "2") (pinfunction "2_2") (pintype "bidirectional"))
    )
    (net (code "43") (name "J9-D") (class "Default")
      (node (ref "IC1") (pin "14") (pinfunction "PB2(SS/OC1B)_14") (pintype "bidirectional"))
      (node (ref "R-PULLUP-10") (pin "1") (pinfunction "1_1") (pintype "passive"))
      (node (ref "RJ-12-9") (pin "3") (pinfunction "3_3") (pintype "bidirectional"))
    )
    (net (code "44") (name "J10-A") (class "Default")
      (node (ref "RJ-12-10") (pin "2") (pinfunction "2_2") (pintype "bidirectional"))
    )
    (net (code "45") (name "J11-A") (class "Default")
      (node (ref "RJ-12-11") (pin "2") (pinfunction "2_2") (pintype "bidirectional"))
    )
    (net (code "46") (name "MISO-J11-D") (class "Default")
      (node (ref "IC1") (pin "16") (pinfunction "PB4(MISO)_16") (pintype "bidirectional"))
      (node (ref "R-PULLUP-12") (pin "1") (pinfunction "1_1") (pintype "passive"))
      (node (ref "RJ-12-11") (pin "3") (pinfunction "3_3") (pintype "bidirectional"))
      (node (ref "SV1") (pin "1") (pinfunction "1_1") (pintype "passive"))
    )
    (net (code "47") (name "MOSI-J10-D") (class "Default")
      (node (ref "IC1") (pin "15") (pinfunction "PB3(MOSI/OC2)_15") (pintype "bidirectional"))
      (node (ref "R-PULLUP-11") (pin "1") (pinfunction "1_1") (pintype "passive"))
      (node (ref "RJ-12-10") (pin "3") (pinfunction "3_3") (pintype "bidirectional"))
      (node (ref "SV1") (pin "4") (pinfunction "4_4") (pintype "passive"))
    )
    (net (code "48") (name "N$19") (class "Default")
      (node (ref "ETH1") (pin "A1") (pinfunction "LED-G-A_A1") (pintype "bidirectional"))
    )
    (net (code "49") (name "N$20") (class "Default")
      (node (ref "ETH1") (pin "C1") (pinfunction "LED-G-K_C1") (pintype "bidirectional"))
    )
    (net (code "50") (name "N$21") (class "Default")
      (node (ref "ETH1") (pin "A2") (pinfunction "LED-Y-A_A2") (pintype "bidirectional"))
    )
    (net (code "51") (name "N$22") (class "Default")
      (node (ref "ETH1") (pin "C2") (pinfunction "LED-Y-K_C2") (pintype "bidirectional"))
    )
    (net (code "52") (name "Net-(ETH1-P2-CT-COMMON)") (class "Default")
      (node (ref "ETH1") (pin "2") (pinfunction "P2-CT-COMMON_2") (pintype "bidirectional"))
      (node (ref "R-CT-COMMON") (pin "2") (pinfunction "2_2") (pintype "passive"))
    )
    (net (code "53") (name "Net-(IC1-PB6(XTAL1{slash}TOSC1))") (class "Default")
      (node (ref "C2") (pin "2") (pinfunction "2_2") (pintype "passive"))
      (node (ref "IC1") (pin "7") (pinfunction "PB6(XTAL1/TOSC1)_7") (pintype "bidirectional"))
      (node (ref "Q1") (pin "2") (pinfunction "2_2") (pintype "passive"))
    )
    (net (code "54") (name "Net-(IC1-PB7(XTAL2{slash}TOSC2))") (class "Default")
      (node (ref "C3") (pin "2") (pinfunction "2_2") (pintype "passive"))
      (node (ref "IC1") (pin "8") (pinfunction "PB7(XTAL2/TOSC2)_8") (pintype "bidirectional"))
      (node (ref "Q1") (pin "1") (pinfunction "1_1") (pintype "passive"))
    )
    (net (code "55") (name "Net-(JP1-Pad2)") (class "Default")
      (node (ref "JP1") (pin "2") (pinfunction "2_2") (pintype "passive"))
      (node (ref "R-PULLUP-2") (pin "2") (pinfunction "2_2") (pintype "passive"))
    )
    (net (code "56") (name "Net-(JP2-Pad2)") (class "Default")
      (node (ref "JP2") (pin "2") (pinfunction "2_2") (pintype "passive"))
      (node (ref "R-PULLUP-3") (pin "2") (pinfunction "2_2") (pintype "passive"))
    )
    (net (code "57") (name "Net-(JP3-Pad2)") (class "Default")
      (node (ref "JP3") (pin "2") (pinfunction "2_2") (pintype "passive"))
      (node (ref "R-PULLUP-4") (pin "2") (pinfunction "2_2") (pintype "passive"))
    )
    (net (code "58") (name "Net-(JP4-Pad2)") (class "Default")
      (node (ref "JP4") (pin "2") (pinfunction "2_2") (pintype "passive"))
      (node (ref "R-PULLUP-5") (pin "2") (pinfunction "2_2") (pintype "passive"))
    )
    (net (code "59") (name "Net-(JP5-Pad2)") (class "Default")
      (node (ref "JP5") (pin "2") (pinfunction "2_2") (pintype "passive"))
      (node (ref "R-PULLUP-6") (pin "2") (pinfunction "2_2") (pintype "passive"))
    )
    (net (code "60") (name "Net-(JP6-Pad2)") (class "Default")
      (node (ref "JP6") (pin "2") (pinfunction "2_2") (pintype "passive"))
      (node (ref "R-PULLUP-7") (pin "2") (pinfunction "2_2") (pintype "passive"))
    )
    (net (code "61") (name "Net-(JP7-Pad2)") (class "Default")
      (node (ref "JP7") (pin "2") (pinfunction "2_2") (pintype "passive"))
      (node (ref "R-PULLUP-8") (pin "2") (pinfunction "2_2") (pintype "passive"))
    )
    (net (code "62") (name "Net-(JP8-Pad2)") (class "Default")
      (node (ref "JP8") (pin "2") (pinfunction "2_2") (pintype "passive"))
      (node (ref "R-PULLUP-9") (pin "2") (pinfunction "2_2") (pintype "passive"))
    )
    (net (code "63") (name "Net-(JP9-Pad2)") (class "Default")
      (node (ref "JP9") (pin "2") (pinfunction "2_2") (pintype "passive"))
      (node (ref "R-PULLUP-10") (pin "2") (pinfunction "2_2") (pintype "passive"))
    )
    (net (code "64") (name "Net-(JP10-Pad2)") (class "Default")
      (node (ref "JP10") (pin "2") (pinfunction "2_2") (pintype "passive"))
      (node (ref "R-PULLUP-11") (pin "2") (pinfunction "2_2") (pintype "passive"))
    )
    (net (code "65") (name "Net-(JP11-Pad2)") (class "Default")
      (node (ref "JP11") (pin "2") (pinfunction "2_2") (pintype "passive"))
      (node (ref "R-PULLUP-12") (pin "2") (pinfunction "2_2") (pintype "passive"))
    )
    (net (code "66") (name "Net-(JP12-Pad2)") (class "Default")
      (node (ref "JP12") (pin "2") (pinfunction "2_2") (pintype "passive"))
      (node (ref "R3") (pin "2") (pinfunction "2_2") (pintype "passive"))
    )
    (net (code "67") (name "Net-(JP13-Pad2)") (class "Default")
      (node (ref "JP13") (pin "2") (pinfunction "2_2") (pintype "passive"))
      (node (ref "R-PULLUP-13") (pin "2") (pinfunction "2_2") (pintype "passive"))
    )
    (net (code "68") (name "Net-(JP14-Pad2)") (class "Default")
      (node (ref "JP14") (pin "2") (pinfunction "2_2") (pintype "passive"))
      (node (ref "R-PULLUP-14") (pin "2") (pinfunction "2_2") (pintype "passive"))
    )
    (net (code "69") (name "Net-(LED1-PadA)") (class "Default")
      (node (ref "LED1") (pin "A") (pinfunction "A_A") (pintype "passive"))
      (node (ref "R1") (pin "1") (pinfunction "1_1") (pintype "passive"))
    )
    (net (code "70") (name "Net-(LED2-PadA)") (class "Default")
      (node (ref "LED2") (pin "A") (pinfunction "A_A") (pintype "passive"))
      (node (ref "R2") (pin "1") (pinfunction "1_1") (pintype "passive"))
    )
    (net (code "71") (name "Net-(LED3-PadA)") (class "Default")
      (node (ref "LED3") (pin "A") (pinfunction "A_A") (pintype "passive"))
      (node (ref "R3") (pin "1") (pinfunction "1_1") (pintype "passive"))
    )
    (net (code "72") (name "Net-(LED4-PadA)") (class "Default")
      (node (ref "LED4") (pin "A") (pinfunction "A_A") (pintype "passive"))
      (node (ref "R4") (pin "1") (pinfunction "1_1") (pintype "passive"))
    )
    (net (code "73") (name "Net-(U$1-ADJ)") (class "Default")
      (node (ref "R-ADJ-DEC") (pin "2") (pinfunction "2_2") (pintype "passive"))
      (node (ref "R-ADJ-INC") (pin "2") (pinfunction "2_2") (pintype "passive"))
      (node (ref "U$1") (pin "P$9") (pinfunction "ADJ_P$9") (pintype "bidirectional"))
    )
    (net (code "74") (name "Net-(U$1-CP1)") (class "Default")
      (node (ref "R-CLASS") (pin "2") (pinfunction "2_2") (pintype "passive"))
      (node (ref "U$1") (pin "P$5") (pinfunction "CP1_P$5") (pintype "bidirectional"))
    )
    (net (code "75") (name "Net-(U$1-CP2)") (class "Default")
      (node (ref "R-CLASS") (pin "1") (pinfunction "1_1") (pintype "passive"))
      (node (ref "U$1") (pin "P$6") (pinfunction "CP2_P$6") (pintype "bidirectional"))
    )
    (net (code "76") (name "RD+") (class "Default")
      (node (ref "ETH1") (pin "4") (pinfunction "P4-RD+_4") (pintype "bidirectional"))
      (node (ref "X1") (pin "3") (pinfunction "S_3") (pintype "passive"))
    )
    (net (code "77") (name "RD-") (class "Default")
      (node (ref "ETH1") (pin "5") (pinfunction "P5-RD-_5") (pintype "bidirectional"))
      (node (ref "X1") (pin "4") (pinfunction "S_4") (pintype "passive"))
    )
    (net (code "78") (name "RPI-CS0") (class "Default")
      (node (ref "R-PI-3B1") (pin "P$24") (pinfunction "GPIO-8_P$24") (pintype "bidirectional"))
    )
    (net (code "79") (name "RPI-CS1") (class "Default")
      (node (ref "R-PI-3B1") (pin "P$26") (pinfunction "GPIO-7_P$26") (pintype "bidirectional"))
    )
    (net (code "80") (name "RPI-MISO") (class "Default")
      (node (ref "R-PI-3B1") (pin "P$21") (pinfunction "GPIO-9_P$21") (pintype "bidirectional"))
    )
    (net (code "81") (name "RPI-MOSI") (class "Default")
      (node (ref "R-PI-3B1") (pin "P$19") (pinfunction "GPIO-10_P$19") (pintype "bidirectional"))
    )
    (net (code "82") (name "RPI-RXD_ATMEGA-TXD") (class "Default")
      (node (ref "IC1") (pin "31") (pinfunction "PD1(TXD)_31") (pintype "bidirectional"))
      (node (ref "R-PI-3B1") (pin "P$10") (pinfunction "GPIO-15_P$10") (pintype "bidirectional"))
    )
    (net (code "83") (name "RPI-SCK") (class "Default")
      (node (ref "R-PI-3B1") (pin "P$23") (pinfunction "GPIO-11_P$23") (pintype "bidirectional"))
    )
    (net (code "84") (name "RPI-TXD_ATMEGA-RXD") (class "Default")
      (node (ref "IC1") (pin "30") (pinfunction "PD0(RXD)_30") (pintype "bidirectional"))
      (node (ref "R-PI-3B1") (pin "P$8") (pinfunction "GPIO-14_P$8") (pintype "bidirectional"))
    )
    (net (code "85") (name "SCK-J7-A") (class "Default")
      (node (ref "IC1") (pin "17") (pinfunction "PB5(SCK)_17") (pintype "bidirectional"))
      (node (ref "JP12") (pin "1") (pinfunction "1_1") (pintype "passive"))
      (node (ref "RJ-12-7") (pin "2") (pinfunction "2_2") (pintype "bidirectional"))
      (node (ref "SV1") (pin "3") (pinfunction "3_3") (pintype "passive"))
    )
    (net (code "86") (name "STATUS-RPI") (class "Default")
      (node (ref "R-PI-3B1") (pin "P$3") (pinfunction "GPIO-2_P$3") (pintype "bidirectional"))
      (node (ref "R2") (pin "2") (pinfunction "2_2") (pintype "passive"))
    )
    (net (code "87") (name "TD+") (class "Default")
      (node (ref "ETH1") (pin "1") (pinfunction "P1-TD+_1") (pintype "bidirectional"))
      (node (ref "X1") (pin "1") (pinfunction "S_1") (pintype "passive"))
    )
    (net (code "88") (name "TD-") (class "Default")
      (node (ref "ETH1") (pin "3") (pinfunction "P3-TD-_3") (pintype "bidirectional"))
      (node (ref "X1") (pin "2") (pinfunction "S_2") (pintype "passive"))
    )
    (net (code "89") (name "VC+A") (class "Default")
      (node (ref "ETH1") (pin "8") (pinfunction "P8-VC+_8") (pintype "bidirectional"))
      (node (ref "U$1") (pin "P$1") (pinfunction "VA1_P$1") (pintype "input"))
    )
    (net (code "90") (name "VC+B") (class "Default")
      (node (ref "ETH1") (pin "10") (pinfunction "P10-VC+_10") (pintype "bidirectional"))
      (node (ref "U$1") (pin "P$3") (pinfunction "VB1_P$3") (pintype "input"))
    )
    (net (code "91") (name "VC-A") (class "Default")
      (node (ref "ETH1") (pin "9") (pinfunction "P9-VC-_9") (pintype "bidirectional"))
      (node (ref "U$1") (pin "P$2") (pinfunction "VA2_P$2") (pintype "input"))
    )
    (net (code "92") (name "VC-B") (class "Default")
      (node (ref "ETH1") (pin "11") (pinfunction "P11-VC-_11") (pintype "bidirectional"))
      (node (ref "U$1") (pin "P$4") (pinfunction "VB2_P$4") (pintype "input"))
    )
    (net (code "93") (name "unconnected-(R-PI-3B1-+3V3-PadP$1)") (class "Default")
      (node (ref "R-PI-3B1") (pin "P$1") (pinfunction "+3V3_P$1") (pintype "bidirectional"))
    )
    (net (code "94") (name "unconnected-(R-PI-3B1-+3V3-PadP$17)") (class "Default")
      (node (ref "R-PI-3B1") (pin "P$17") (pinfunction "+3V3_P$17") (pintype "bidirectional"))
    )
  )
)
